# as_wounds.net
KiCad netlist of a schematic drawn in EAGLE
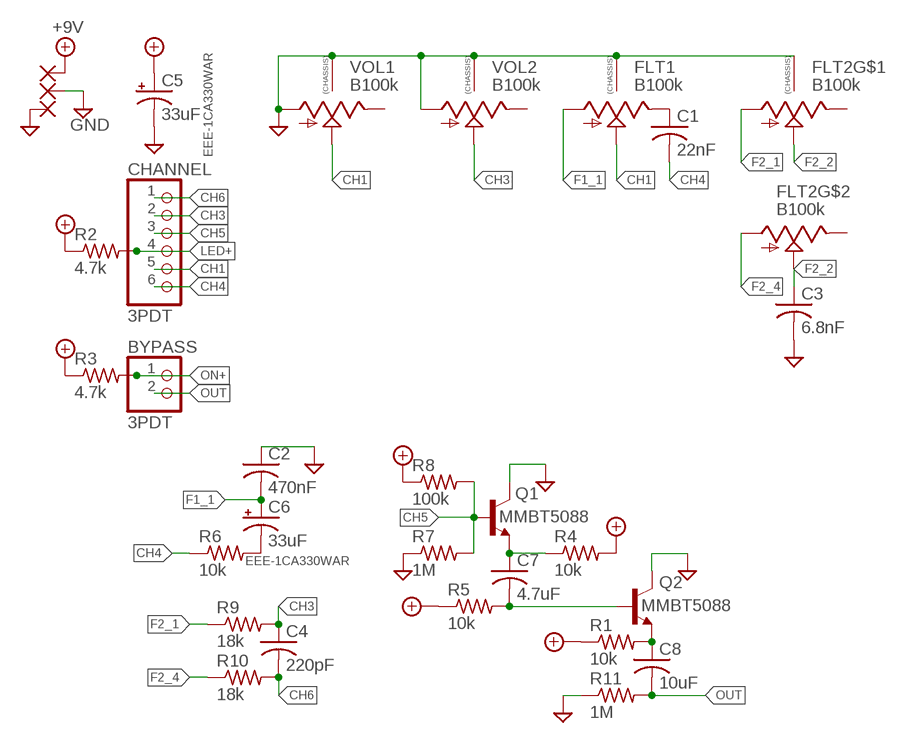
[diagram p0: schematic, sheet 1]

(export (version "E")
  (design (tool "Eeschema 10.0.6"))
  (components
    (comp (ref "BYPASS")
      (value "3PDT")
      (footprint "eagle-import:1X02")
      (libsource (lib "eagle-import") (part "PINHD-1X2"))
    )
    (comp (ref "C1")
      (value "22nF")
      (footprint "eagle-import:C0603")
      (libsource (lib "eagle-import") (part "C-USC0603"))
    )
    (comp (ref "C2")
      (value "470nF")
      (footprint "eagle-import:C0603")
      (libsource (lib "eagle-import") (part "C-USC0603"))
    )
    (comp (ref "C3")
      (value "6.8nF")
      (footprint "eagle-import:C0603")
      (libsource (lib "eagle-import") (part "C-USC0603"))
    )
    (comp (ref "C4")
      (value "220pF")
      (footprint "eagle-import:C0603")
      (libsource (lib "eagle-import") (part "C-USC0603"))
    )
    (comp (ref "C5")
      (value "33uF")
      (footprint "eagle-import:PANASONIC_C")
      (libsource (lib "eagle-import") (part "22UF-POLAR-PANASONIC_C-35V-20%"))
    )
    (comp (ref "C6")
      (value "33uF")
      (footprint "eagle-import:PANASONIC_C")
      (libsource (lib "eagle-import") (part "22UF-POLAR-PANASONIC_C-35V-20%"))
    )
    (comp (ref "C7")
      (value "4.7uF")
      (footprint "eagle-import:C1206")
      (libsource (lib "eagle-import") (part "C-USC1206"))
    )
    (comp (ref "C8")
      (value "10uF")
      (footprint "eagle-import:C1206")
      (libsource (lib "eagle-import") (part "C-USC1206"))
    )
    (comp (ref "CHANNEL")
      (value "3PDT")
      (footprint "eagle-import:1X06")
      (libsource (lib "eagle-import") (part "PINHD-1X6"))
    )
    (comp (ref "FLT1")
      (value "B100k")
      (footprint "eagle-import:9MM_SNAP-IN_POT")
      (libsource (lib "eagle-import") (part "9MM_SNAP-IN_POT_CHASSIS"))
    )
    (comp (ref "FLT2")
      (value "B100k")
      (footprint "eagle-import:DUAL_9MM_SNAP-IN_POT")
      (libsource (lib "eagle-import") (part "ALPHA-9MM-DUALPOT"))
    )
    (comp (ref "PAD1")
      (value "1,6/0,8")
      (footprint "eagle-import:1,6_0,8")
      (libsource (lib "eagle-import") (part "1,6/0,8"))
    )
    (comp (ref "PAD2")
      (value "1,6/0,8")
      (footprint "eagle-import:1,6_0,8")
      (libsource (lib "eagle-import") (part "1,6/0,8"))
    )
    (comp (ref "PAD3")
      (value "1,6/0,8")
      (footprint "eagle-import:1,6_0,8")
      (libsource (lib "eagle-import") (part "1,6/0,8"))
    )
    (comp (ref "Q1")
      (value "MMBT5088")
      (footprint "eagle-import:SOT23-BEC")
      (fields (field (name "MF") "ON Semiconductor"))
      (libsource (lib "eagle-import") (part "MMBT5088"))
    )
    (comp (ref "Q2")
      (value "MMBT5088")
      (footprint "eagle-import:SOT23-BEC")
      (fields (field (name "MF") "ON Semiconductor"))
      (libsource (lib "eagle-import") (part "MMBT5088"))
    )
    (comp (ref "R1")
      (value "10k")
      (footprint "eagle-import:R0603")
      (libsource (lib "eagle-import") (part "R-US_R0603"))
    )
    (comp (ref "R2")
      (value "4.7k")
      (footprint "eagle-import:R0603")
      (libsource (lib "eagle-import") (part "R-US_R0603"))
    )
    (comp (ref "R3")
      (value "4.7k")
      (footprint "eagle-import:R0603")
      (libsource (lib "eagle-import") (part "R-US_R0603"))
    )
    (comp (ref "R4")
      (value "10k")
      (footprint "eagle-import:R0603")
      (libsource (lib "eagle-import") (part "R-US_R0603"))
    )
    (comp (ref "R5")
      (value "10k")
      (footprint "eagle-import:R0603")
      (libsource (lib "eagle-import") (part "R-US_R0603"))
    )
    (comp (ref "R6")
      (value "10k")
      (footprint "eagle-import:R0603")
      (libsource (lib "eagle-import") (part "R-US_R0603"))
    )
    (comp (ref "R7")
      (value "1M")
      (footprint "eagle-import:R0603")
      (libsource (lib "eagle-import") (part "R-US_R0603"))
    )
    (comp (ref "R8")
      (value "100k")
      (footprint "eagle-import:R0603")
      (libsource (lib "eagle-import") (part "R-US_R0603"))
    )
    (comp (ref "R9")
      (value "18k")
      (footprint "eagle-import:R0603")
      (libsource (lib "eagle-import") (part "R-US_R0603"))
    )
    (comp (ref "R10")
      (value "18k")
      (footprint "eagle-import:R0603")
      (libsource (lib "eagle-import") (part "R-US_R0603"))
    )
    (comp (ref "R11")
      (value "1M")
      (footprint "eagle-import:R0603")
      (libsource (lib "eagle-import") (part "R-US_R0603"))
    )
    (comp (ref "VOL1")
      (value "B100k")
      (footprint "eagle-import:9MM_SNAP-IN_POT")
      (libsource (lib "eagle-import") (part "9MM_SNAP-IN_POT_CHASSIS"))
    )
    (comp (ref "VOL2")
      (value "B100k")
      (footprint "eagle-import:9MM_SNAP-IN_POT")
      (libsource (lib "eagle-import") (part "9MM_SNAP-IN_POT_CHASSIS"))
    )
  )
  (nets
    (net (code "1") (name "+9V") (class "Default")
      (node (ref "C5") (pin "+") (pinfunction "+_+") (pintype "passive"))
      (node (ref "PAD1") (pin "1") (pinfunction "P_1") (pintype "passive"))
      (node (ref "R1") (pin "1") (pinfunction "1_1") (pintype "passive"))
      (node (ref "R2") (pin "1") (pinfunction "1_1") (pintype "passive"))
      (node (ref "R3") (pin "1") (pinfunction "1_1") (pintype "passive"))
      (node (ref "R4") (pin "2") (pinfunction "2_2") (pintype "passive"))
      (node (ref "R5") (pin "1") (pinfunction "1_1") (pintype "passive"))
      (node (ref "R8") (pin "1") (pinfunction "1_1") (pintype "passive"))
    )
    (net (code "2") (name "CH1") (class "Default")
      (node (ref "CHANNEL") (pin "5") (pinfunction "5_5") (pintype "passive"))
      (node (ref "FLT1") (pin "2") (pinfunction "S_2") (pintype "passive"))
      (node (ref "VOL1") (pin "2") (pinfunction "S_2") (pintype "passive"))
    )
    (net (code "3") (name "CH3") (class "Default")
      (node (ref "C4") (pin "1") (pinfunction "1_1") (pintype "passive"))
      (node (ref "CHANNEL") (pin "2") (pinfunction "2_2") (pintype "passive"))
      (node (ref "R9") (pin "2") (pinfunction "2_2") (pintype "passive"))
      (node (ref "VOL2") (pin "2") (pinfunction "S_2") (pintype "passive"))
    )
    (net (code "4") (name "CH4") (class "Default")
      (node (ref "C1") (pin "2") (pinfunction "2_2") (pintype "passive"))
      (node (ref "CHANNEL") (pin "6") (pinfunction "6_6") (pintype "passive"))
      (node (ref "R6") (pin "1") (pinfunction "1_1") (pintype "passive"))
    )
    (net (code "5") (name "CH5") (class "Default")
      (node (ref "CHANNEL") (pin "3") (pinfunction "3_3") (pintype "passive"))
      (node (ref "Q1") (pin "B") (pinfunction "B_B") (pintype "passive"))
      (node (ref "R7") (pin "2") (pinfunction "2_2") (pintype "passive"))
      (node (ref "R8") (pin "2") (pinfunction "2_2") (pintype "passive"))
    )
    (net (code "6") (name "CH6") (class "Default")
      (node (ref "C4") (pin "2") (pinfunction "2_2") (pintype "passive"))
      (node (ref "CHANNEL") (pin "1") (pinfunction "1_1") (pintype "passive"))
      (node (ref "R10") (pin "2") (pinfunction "2_2") (pintype "passive"))
    )
    (net (code "7") (name "F1_1") (class "Default")
      (node (ref "C2") (pin "2") (pinfunction "2_2") (pintype "passive"))
      (node (ref "C6") (pin "+") (pinfunction "+_+") (pintype "passive"))
      (node (ref "FLT1") (pin "1") (pinfunction "A_1") (pintype "passive"))
    )
    (net (code "8") (name "F2_1") (class "Default")
      (node (ref "FLT2") (pin "1") (pinfunction "A_1") (pintype "passive"))
      (node (ref "R9") (pin "1") (pinfunction "1_1") (pintype "passive"))
    )
    (net (code "9") (name "F2_2") (class "Default")
      (node (ref "C3") (pin "1") (pinfunction "1_1") (pintype "passive"))
      (node (ref "FLT2") (pin "2") (pinfunction "S_2") (pintype "passive"))
      (node (ref "FLT2") (pin "2B") (pinfunction "S_2B") (pintype "passive"))
    )
    (net (code "10") (name "F2_4") (class "Default")
      (node (ref "FLT2") (pin "1B") (pinfunction "A_1B") (pintype "passive"))
      (node (ref "R10") (pin "1") (pinfunction "1_1") (pintype "passive"))
    )
    (net (code "11") (name "GND") (class "Default")
      (node (ref "C2") (pin "1") (pinfunction "1_1") (pintype "passive"))
      (node (ref "C3") (pin "2") (pinfunction "2_2") (pintype "passive"))
      (node (ref "C5") (pin "-") (pinfunction "-_-") (pintype "passive"))
      (node (ref "FLT1") (pin "CHASSIS1") (pinfunction "P$1_CHASSIS1") (pintype "passive"))
      (node (ref "FLT1") (pin "CHASSIS2") (pinfunction "P$1_CHASSIS2") (pintype "passive"))
      (node (ref "FLT2") (pin "CHASSIS1") (pinfunction "P$1_CHASSIS1") (pintype "passive"))
      (node (ref "FLT2") (pin "CHASSIS2") (pinfunction "P$1_CHASSIS2") (pintype "passive"))
      (node (ref "PAD2") (pin "1") (pinfunction "P_1") (pintype "passive"))
      (node (ref "PAD3") (pin "1") (pinfunction "P_1") (pintype "passive"))
      (node (ref "Q1") (pin "C") (pinfunction "C_C") (pintype "passive"))
      (node (ref "Q2") (pin "C") (pinfunction "C_C") (pintype "passive"))
      (node (ref "R11") (pin "1") (pinfunction "1_1") (pintype "passive"))
      (node (ref "R7") (pin "1") (pinfunction "1_1") (pintype "passive"))
      (node (ref "VOL1") (pin "1") (pinfunction "A_1") (pintype "passive"))
      (node (ref "VOL1") (pin "CHASSIS1") (pinfunction "P$1_CHASSIS1") (pintype "passive"))
      (node (ref "VOL1") (pin "CHASSIS2") (pinfunction "P$1_CHASSIS2") (pintype "passive"))
      (node (ref "VOL2") (pin "1") (pinfunction "A_1") (pintype "passive"))
      (node (ref "VOL2") (pin "CHASSIS1") (pinfunction "P$1_CHASSIS1") (pintype "passive"))
      (node (ref "VOL2") (pin "CHASSIS2") (pinfunction "P$1_CHASSIS2") (pintype "passive"))
    )
    (net (code "12") (name "LED+") (class "Default")
      (node (ref "CHANNEL") (pin "4") (pinfunction "4_4") (pintype "passive"))
      (node (ref "R2") (pin "2") (pinfunction "2_2") (pintype "passive"))
    )
    (net (code "13") (name "Net-(C6-Pad-)") (class "Default")
      (node (ref "C6") (pin "-") (pinfunction "-_-") (pintype "passive"))
      (node (ref "R6") (pin "2") (pinfunction "2_2") (pintype "passive"))
    )
    (net (code "14") (name "Net-(C7-Pad1)") (class "Default")
      (node (ref "C7") (pin "1") (pinfunction "1_1") (pintype "passive"))
      (node (ref "Q1") (pin "E") (pinfunction "E_E") (pintype "passive"))
      (node (ref "R4") (pin "1") (pinfunction "1_1") (pintype "passive"))
    )
    (net (code "15") (name "Net-(C7-Pad2)") (class "Default")
      (node (ref "C7") (pin "2") (pinfunction "2_2") (pintype "passive"))
      (node (ref "Q2") (pin "B") (pinfunction "B_B") (pintype "passive"))
      (node (ref "R5") (pin "2") (pinfunction "2_2") (pintype "passive"))
    )
    (net (code "16") (name "Net-(C8-Pad1)") (class "Default")
      (node (ref "C8") (pin "1") (pinfunction "1_1") (pintype "passive"))
      (node (ref "Q2") (pin "E") (pinfunction "E_E") (pintype "passive"))
      (node (ref "R1") (pin "2") (pinfunction "2_2") (pintype "passive"))
    )
    (net (code "17") (name "Net-(FLT1-E)") (class "Default")
      (node (ref "C1") (pin "1") (pinfunction "1_1") (pintype "passive"))
      (node (ref "FLT1") (pin "3") (pinfunction "E_3") (pintype "passive"))
    )
    (net (code "18") (name "ON+") (class "Default")
      (node (ref "BYPASS") (pin "1") (pinfunction "1_1") (pintype "passive"))
      (node (ref "R3") (pin "2") (pinfunction "2_2") (pintype "passive"))
    )
    (net (code "19") (name "OUT") (class "Default")
      (node (ref "BYPASS") (pin "2") (pinfunction "2_2") (pintype "passive"))
      (node (ref "C8") (pin "2") (pinfunction "2_2") (pintype "passive"))
      (node (ref "R11") (pin "2") (pinfunction "2_2") (pintype "passive"))
    )
    (net (code "20") (name "unconnected-(FLT2A-E-Pad3)") (class "Default")
      (node (ref "FLT2") (pin "3") (pinfunction "E_3") (pintype "passive"))
    )
    (net (code "21") (name "unconnected-(FLT2B-E-Pad3B)") (class "Default")
      (node (ref "FLT2") (pin "3B") (pinfunction "E_3B") (pintype "passive"))
    )
    (net (code "22") (name "unconnected-(VOL1-E-Pad3)") (class "Default")
      (node (ref "VOL1") (pin "3") (pinfunction "E_3") (pintype "passive"))
    )
    (net (code "23") (name "unconnected-(VOL2-E-Pad3)") (class "Default")
      (node (ref "VOL2") (pin "3") (pinfunction "E_3") (pintype "passive"))
    )
  )
)
